# Mag_Encoder_KMZ60.net
KiCad netlist of a schematic drawn in Altium Designer
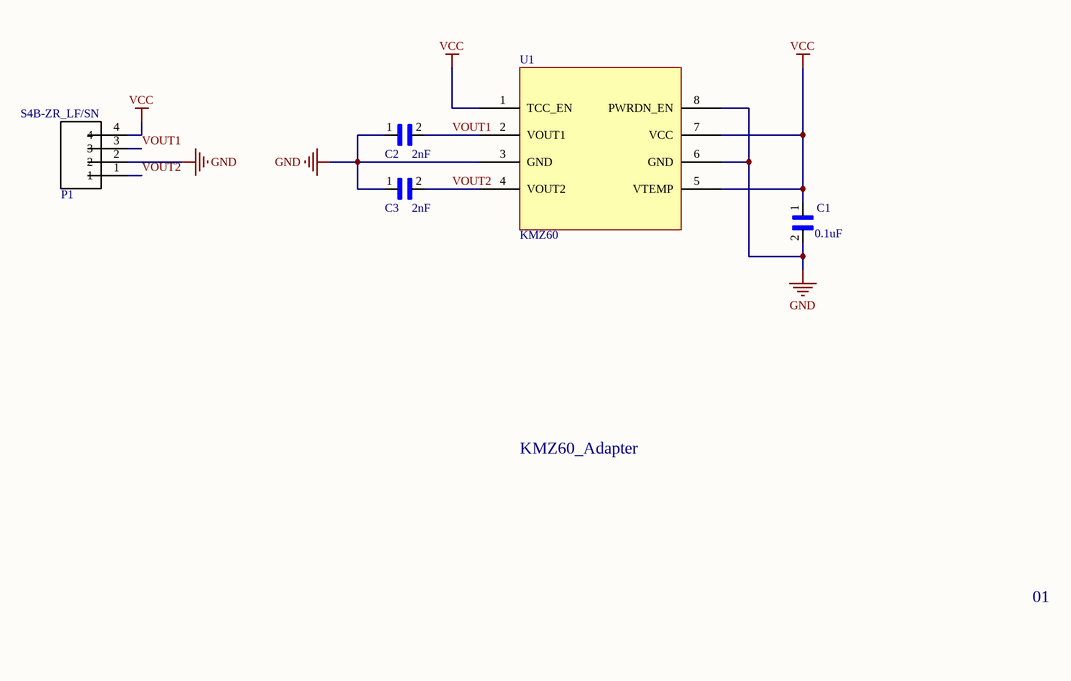
[diagram p0: Mag_Encoder_KMZ60.SchDoc]

(export (version "E")
  (design (tool "Eeschema 10.0.6"))
  (components
    (comp (ref "C1")
      (value "0.1uF")
      (footprint "*CAPC1608X90N")
      (description "Cap Ceramic 0.1uF 50V X7R 10% Pad SMD 0603 125Â°C T/R")
      (fields (field (name "MF") "Samsung Electro-Mechanics") (field (name "MP") "CL10B104KB8NNNL"))
      (libsource (lib "CL10B104KB8NNNL") (part "CL10B104KB8NNNL"))
    )
    (comp (ref "C2")
      (value "2nF")
      (footprint "*CAPC1608X90N")
      (description "Cap Ceramic 2nF 50V X7R 10% Pad SMD 0603 125Â°C T/R")
      (fields (field (name "MF") "Samsung Electro-Mechanics") (field (name "MP") "CL10B104KB8NNNL"))
      (libsource (lib "CL10B104KB8NNNL") (part "CL10B104KB8NNNL"))
    )
    (comp (ref "C3")
      (value "2nF")
      (footprint "*CAPC1608X90N")
      (description "Cap Ceramic 2nF 50V X7R 10% Pad SMD 0603 125Â°C T/R")
      (fields (field (name "MF") "Samsung Electro-Mechanics") (field (name "MP") "CL10B104KB8NNNL"))
      (libsource (lib "CL10B104KB8NNNL") (part "CL10B104KB8NNNL"))
    )
    (comp (ref "P1")
      (value "S4B-ZR_LF/SN")
      (footprint "*JST_S4B-ZR(LF)(SN)")
      (description "Conn Shrouded Header HDR 4 POS 1.5mm Solder RA Thru-Hole Box")
      (fields (field (name "MP") "S4B-ZR _LF__SN_") (field (name "MF") "JST Sales"))
      (libsource (lib "S4B-ZR__LF__SN_") (part "S4B-ZR_(LF)(SN)"))
    )
    (comp (ref "U1")
      (value "KMZ60")
      (footprint "SOIC127P600X175-8N")
      (fields (field (name "MANUFACTURER") "NXP"))
      (libsource (lib "NXP") (part "KVM60"))
    )
  )
  (nets
    (net (code "1") (name "/VOUT1") (class "Default")
      (node (ref "C2") (pin "2") (pinfunction "2_2") (pintype "passive"))
      (node (ref "P1") (pin "3") (pinfunction "3_3") (pintype "passive"))
      (node (ref "U1") (pin "2") (pinfunction "VOUT1_2") (pintype "passive"))
    )
    (net (code "2") (name "/VOUT2") (class "Default")
      (node (ref "C3") (pin "2") (pinfunction "2_2") (pintype "passive"))
      (node (ref "P1") (pin "1") (pinfunction "1_1") (pintype "passive"))
      (node (ref "U1") (pin "4") (pinfunction "VOUT2_4") (pintype "passive"))
    )
    (net (code "3") (name "GND") (class "Default")
      (node (ref "C1") (pin "2") (pinfunction "2_2") (pintype "passive"))
      (node (ref "C2") (pin "1") (pinfunction "1_1") (pintype "passive"))
      (node (ref "C3") (pin "1") (pinfunction "1_1") (pintype "passive"))
      (node (ref "P1") (pin "2") (pinfunction "2_2") (pintype "passive"))
      (node (ref "U1") (pin "3") (pinfunction "GND_3") (pintype "passive"))
      (node (ref "U1") (pin "6") (pinfunction "GND_6") (pintype "passive"))
      (node (ref "U1") (pin "8") (pinfunction "PWRDN_EN_8") (pintype "passive"))
    )
    (net (code "4") (name "VCC") (class "Default")
      (node (ref "C1") (pin "1") (pinfunction "1_1") (pintype "passive"))
      (node (ref "P1") (pin "4") (pinfunction "4_4") (pintype "passive"))
      (node (ref "U1") (pin "1") (pinfunction "TCC_EN_1") (pintype "passive"))
      (node (ref "U1") (pin "5") (pinfunction "VTEMP_5") (pintype "passive"))
      (node (ref "U1") (pin "7") (pinfunction "VCC_7") (pintype "passive"))
    )
  )
)
